# smd-to-breadboard.net
KiCad netlist of a schematic drawn in EAGLE
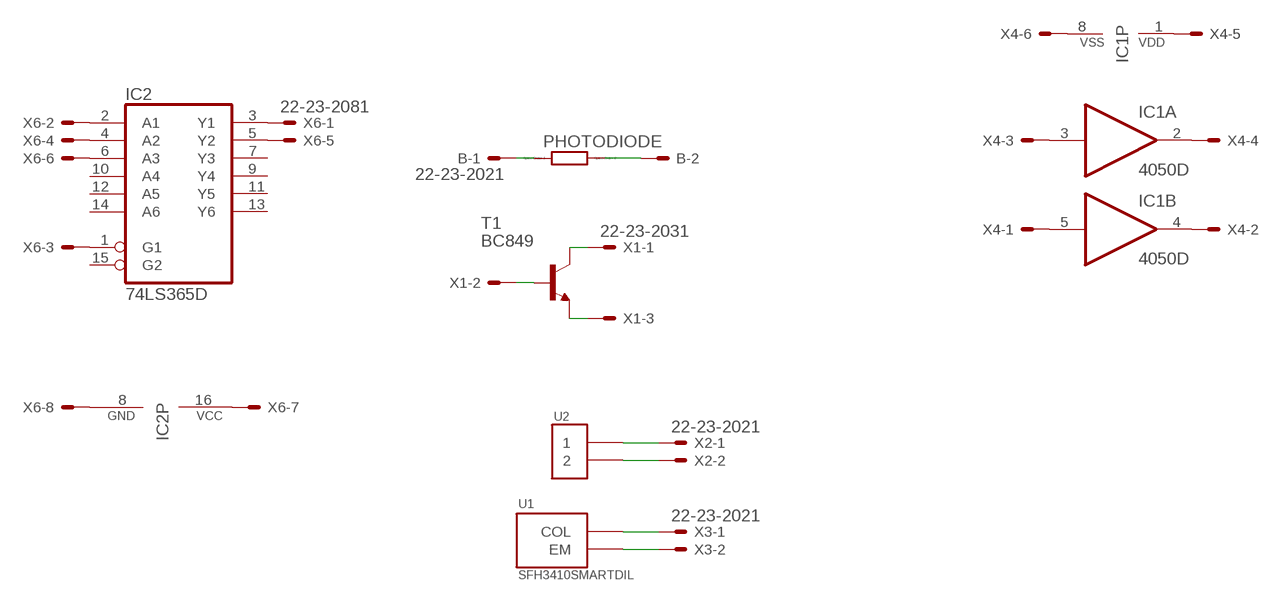
[diagram p0: schematic, sheet 1]

(export (version "E")
  (design (tool "Eeschema 10.0.6"))
  (components
    (comp (ref "B")
      (value "22-23-2021")
      (footprint "eagle-import:22-23-2021")
      (fields (field (name "MF") "MOLEX"))
      (libsource (lib "eagle-import") (part "22-23-2021"))
    )
    (comp (ref "IC1")
      (value "4050D")
      (footprint "eagle-import:SO16")
      (libsource (lib "eagle-import") (part "4050D"))
    )
    (comp (ref "IC2")
      (value "74LS365D")
      (footprint "eagle-import:SO16")
      (libsource (lib "eagle-import") (part "74365DLS"))
    )
    (comp (ref "PHOTODIODE")
      (value "RR1206")
      (footprint "eagle-import:R1206")
      (libsource (lib "eagle-import") (part "RR1206"))
    )
    (comp (ref "T1")
      (value "BC849")
      (footprint "eagle-import:SOT23")
      (libsource (lib "eagle-import") (part "BC849"))
    )
    (comp (ref "U1")
      (value "SFH3410SMARTDIL")
      (footprint "eagle-import:SFH3410")
      (libsource (lib "eagle-import") (part "SFH3410SMARTDIL"))
    )
    (comp (ref "U2")
      (value "LUW-W5AMGULLWING")
      (footprint "eagle-import:LUW-W5AM")
      (libsource (lib "eagle-import") (part "LUW-W5AMGULLWING"))
    )
    (comp (ref "X1")
      (value "22-23-2031")
      (footprint "eagle-import:22-23-2031")
      (fields (field (name "MF") "MOLEX"))
      (libsource (lib "eagle-import") (part "22-23-2031"))
    )
    (comp (ref "X2")
      (value "22-23-2021")
      (footprint "eagle-import:22-23-2021")
      (fields (field (name "MF") "MOLEX"))
      (libsource (lib "eagle-import") (part "22-23-2021"))
    )
    (comp (ref "X3")
      (value "22-23-2021")
      (footprint "eagle-import:22-23-2021")
      (fields (field (name "MF") "MOLEX"))
      (libsource (lib "eagle-import") (part "22-23-2021"))
    )
    (comp (ref "X4")
      (value "22-23-2061")
      (footprint "eagle-import:22-23-2061")
      (fields (field (name "MF") "MOLEX"))
      (libsource (lib "eagle-import") (part "22-23-2061"))
    )
    (comp (ref "X6")
      (value "22-23-2081")
      (footprint "eagle-import:22-23-2081")
      (fields (field (name "MF") "MOLEX"))
      (libsource (lib "eagle-import") (part "22-23-2081"))
    )
  )
  (nets
    (net (code "1") (name "Net-(BA-S)") (class "Default")
      (node (ref "B") (pin "1") (pinfunction "S_1") (pintype "passive"))
      (node (ref "PHOTODIODE") (pin "1") (pinfunction "1_1") (pintype "passive"))
    )
    (net (code "2") (name "Net-(BB-S)") (class "Default")
      (node (ref "B") (pin "2") (pinfunction "S_2") (pintype "passive"))
      (node (ref "PHOTODIODE") (pin "2") (pinfunction "2_2") (pintype "passive"))
    )
    (net (code "3") (name "Net-(IC1A-I)") (class "Default")
      (node (ref "IC1") (pin "3") (pinfunction "I_3") (pintype "input"))
      (node (ref "X4") (pin "3") (pinfunction "S_3") (pintype "passive"))
    )
    (net (code "4") (name "Net-(IC1A-O)") (class "Default")
      (node (ref "IC1") (pin "2") (pinfunction "O_2") (pintype "output"))
      (node (ref "X4") (pin "4") (pinfunction "S_4") (pintype "passive"))
    )
    (net (code "5") (name "Net-(IC1B-I)") (class "Default")
      (node (ref "IC1") (pin "5") (pinfunction "I_5") (pintype "input"))
      (node (ref "X4") (pin "1") (pinfunction "S_1") (pintype "passive"))
    )
    (net (code "6") (name "Net-(IC1B-O)") (class "Default")
      (node (ref "IC1") (pin "4") (pinfunction "O_4") (pintype "output"))
      (node (ref "X4") (pin "2") (pinfunction "S_2") (pintype "passive"))
    )
    (net (code "7") (name "Net-(IC1G-VDD)") (class "Default")
      (node (ref "IC1") (pin "1") (pinfunction "VDD_1") (pintype "power_in"))
      (node (ref "X4") (pin "5") (pinfunction "S_5") (pintype "passive"))
    )
    (net (code "8") (name "Net-(IC1G-VSS)") (class "Default")
      (node (ref "IC1") (pin "8") (pinfunction "VSS_8") (pintype "power_in"))
      (node (ref "X4") (pin "6") (pinfunction "S_6") (pintype "passive"))
    )
    (net (code "9") (name "Net-(IC2A-A1)") (class "Default")
      (node (ref "IC2") (pin "2") (pinfunction "A1_2") (pintype "input"))
      (node (ref "X6") (pin "2") (pinfunction "S_2") (pintype "passive"))
    )
    (net (code "10") (name "Net-(IC2A-A2)") (class "Default")
      (node (ref "IC2") (pin "4") (pinfunction "A2_4") (pintype "input"))
      (node (ref "X6") (pin "4") (pinfunction "S_4") (pintype "passive"))
    )
    (net (code "11") (name "Net-(IC2A-A3)") (class "Default")
      (node (ref "IC2") (pin "6") (pinfunction "A3_6") (pintype "input"))
      (node (ref "X6") (pin "6") (pinfunction "S_6") (pintype "passive"))
    )
    (net (code "12") (name "Net-(IC2A-G1)") (class "Default")
      (node (ref "IC2") (pin "1") (pinfunction "G1_1") (pintype "input"))
      (node (ref "X6") (pin "3") (pinfunction "S_3") (pintype "passive"))
    )
    (net (code "13") (name "Net-(IC2A-Y1)") (class "Default")
      (node (ref "IC2") (pin "3") (pinfunction "Y1_3") (pintype "tri_state"))
      (node (ref "X6") (pin "1") (pinfunction "S_1") (pintype "passive"))
    )
    (net (code "14") (name "Net-(IC2A-Y2)") (class "Default")
      (node (ref "IC2") (pin "5") (pinfunction "Y2_5") (pintype "tri_state"))
      (node (ref "X6") (pin "5") (pinfunction "S_5") (pintype "passive"))
    )
    (net (code "15") (name "Net-(IC2B-GND)") (class "Default")
      (node (ref "IC2") (pin "8") (pinfunction "GND_8") (pintype "power_in"))
      (node (ref "X6") (pin "8") (pinfunction "S_8") (pintype "passive"))
    )
    (net (code "16") (name "Net-(IC2B-VCC)") (class "Default")
      (node (ref "IC2") (pin "16") (pinfunction "VCC_16") (pintype "power_in"))
      (node (ref "X6") (pin "7") (pinfunction "S_7") (pintype "passive"))
    )
    (net (code "17") (name "Net-(T1-B)") (class "Default")
      (node (ref "T1") (pin "1") (pinfunction "B_1") (pintype "passive"))
      (node (ref "X1") (pin "2") (pinfunction "S_2") (pintype "passive"))
    )
    (net (code "18") (name "Net-(T1-C)") (class "Default")
      (node (ref "T1") (pin "3") (pinfunction "C_3") (pintype "passive"))
      (node (ref "X1") (pin "1") (pinfunction "S_1") (pintype "passive"))
    )
    (net (code "19") (name "Net-(T1-E)") (class "Default")
      (node (ref "T1") (pin "2") (pinfunction "E_2") (pintype "passive"))
      (node (ref "X1") (pin "3") (pinfunction "S_3") (pintype "passive"))
    )
    (net (code "20") (name "Net-(U1-COL)") (class "Default")
      (node (ref "U1") (pin "1") (pinfunction "COL_1") (pintype "bidirectional"))
      (node (ref "X3") (pin "1") (pinfunction "S_1") (pintype "passive"))
    )
    (net (code "21") (name "Net-(U1-EM)") (class "Default")
      (node (ref "U1") (pin "2") (pinfunction "EM_2") (pintype "bidirectional"))
      (node (ref "X3") (pin "2") (pinfunction "S_2") (pintype "passive"))
    )
    (net (code "22") (name "Net-(X2A-S)") (class "Default")
      (node (ref "U2") (pin "1") (pinfunction "1_1") (pintype "bidirectional"))
      (node (ref "X2") (pin "1") (pinfunction "S_1") (pintype "passive"))
    )
    (net (code "23") (name "Net-(X2B-S)") (class "Default")
      (node (ref "U2") (pin "2") (pinfunction "2_2") (pintype "bidirectional"))
      (node (ref "X2") (pin "2") (pinfunction "S_2") (pintype "passive"))
    )
    (net (code "24") (name "unconnected-(IC2A-A4-Pad10)") (class "Default")
      (node (ref "IC2") (pin "10") (pinfunction "A4_10") (pintype "input"))
    )
    (net (code "25") (name "unconnected-(IC2A-A5-Pad12)") (class "Default")
      (node (ref "IC2") (pin "12") (pinfunction "A5_12") (pintype "input"))
    )
    (net (code "26") (name "unconnected-(IC2A-A6-Pad14)") (class "Default")
      (node (ref "IC2") (pin "14") (pinfunction "A6_14") (pintype "input"))
    )
    (net (code "27") (name "unconnected-(IC2A-G2-Pad15)") (class "Default")
      (node (ref "IC2") (pin "15") (pinfunction "G2_15") (pintype "input"))
    )
    (net (code "28") (name "unconnected-(IC2A-Y3-Pad7)") (class "Default")
      (node (ref "IC2") (pin "7") (pinfunction "Y3_7") (pintype "tri_state"))
    )
    (net (code "29") (name "unconnected-(IC2A-Y4-Pad9)") (class "Default")
      (node (ref "IC2") (pin "9") (pinfunction "Y4_9") (pintype "tri_state"))
    )
    (net (code "30") (name "unconnected-(IC2A-Y5-Pad11)") (class "Default")
      (node (ref "IC2") (pin "11") (pinfunction "Y5_11") (pintype "tri_state"))
    )
    (net (code "31") (name "unconnected-(IC2A-Y6-Pad13)") (class "Default")
      (node (ref "IC2") (pin "13") (pinfunction "Y6_13") (pintype "tri_state"))
    )
  )
)
